# wifi_sensor.net
KiCad netlist of a schematic drawn in Altium Designer
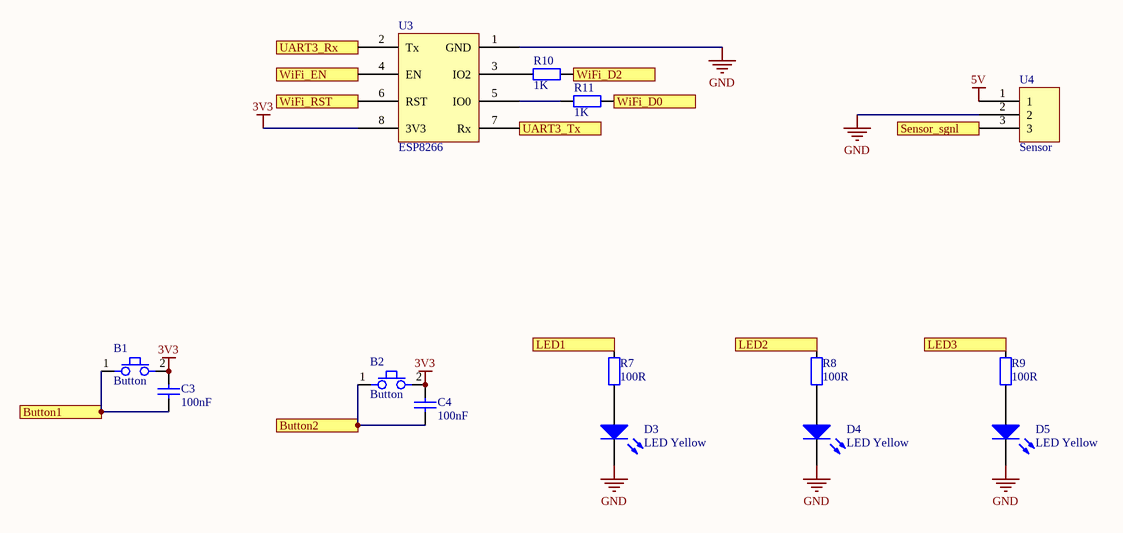
[diagram p0: wifi_sensor.SchDoc]

(export (version "E")
  (design (tool "Eeschema 10.0.6"))
  (components
    (comp (ref "B1") (value "Button") (footprint "Button") (libsource (lib "qlib") (part "Button")))
    (comp (ref "B2") (value "Button") (footprint "Button") (libsource (lib "qlib") (part "Button")))
    (comp (ref "C3")
      (value "100nF")
      (footprint "FP_0805_CAP_085")
      (description "Capacitor")
      (fields (field (name "TOLERANCE") "10%") (field (name "VOLTAGE") "50V"))
      (libsource (lib "hallglib") (part "CAP 100nF"))
    )
    (comp (ref "C4")
      (value "100nF")
      (footprint "FP_0805_CAP_085")
      (description "Capacitor")
      (fields (field (name "TOLERANCE") "10%") (field (name "VOLTAGE") "50V"))
      (libsource (lib "hallglib") (part "CAP 100nF"))
    )
    (comp (ref "D3")
      (value "LED Yellow")
      (footprint "FP_0805_LED_RED")
      (description "Yellow LED")
      (libsource (lib "hallglib") (part "LED Yellow"))
    )
    (comp (ref "D4")
      (value "LED Yellow")
      (footprint "FP_0805_LED_RED")
      (description "Yellow LED")
      (libsource (lib "hallglib") (part "LED Yellow"))
    )
    (comp (ref "D5")
      (value "LED Yellow")
      (footprint "FP_0805_LED_RED")
      (description "Yellow LED")
      (libsource (lib "hallglib") (part "LED Yellow"))
    )
    (comp (ref "R7")
      (value "100R")
      (footprint "FP_0805_RES")
      (description "Resistor")
      (fields (field (name "TOLERANCE") "5%") (field (name "POWER") "125mW"))
      (libsource (lib "hallglib") (part "RES 100R"))
    )
    (comp (ref "R8")
      (value "100R")
      (footprint "FP_0805_RES")
      (description "Resistor")
      (fields (field (name "TOLERANCE") "5%") (field (name "POWER") "125mW"))
      (libsource (lib "hallglib") (part "RES 100R"))
    )
    (comp (ref "R9")
      (value "100R")
      (footprint "FP_0805_RES")
      (description "Resistor")
      (fields (field (name "TOLERANCE") "5%") (field (name "POWER") "125mW"))
      (libsource (lib "hallglib") (part "RES 100R"))
    )
    (comp (ref "R10")
      (value "1K")
      (footprint "FP_0805_RES")
      (description "Resistor")
      (fields (field (name "TOLERANCE") "5%") (field (name "POWER") "125mW"))
      (libsource (lib "hallglib") (part "RES 1K"))
    )
    (comp (ref "R11")
      (value "1K")
      (footprint "FP_0805_RES")
      (description "Resistor")
      (fields (field (name "TOLERANCE") "5%") (field (name "POWER") "125mW"))
      (libsource (lib "hallglib") (part "RES 1K"))
    )
    (comp (ref "U3") (value "ESP8266") (footprint "HDR2X4") (libsource (lib "qlib") (part "ESP8266")))
    (comp (ref "U4") (value "Sensor") (footprint "3P_CONN_2mm") (libsource (lib "qlib") (part "Conn_3P")))
  )
  (nets
    (net (code "1") (name "/Button1") (class "Default")
      (node (ref "B1") (pin "1") (pinfunction "1_1") (pintype "passive"))
      (node (ref "C3") (pin "1") (pinfunction "1_1") (pintype "passive"))
    )
    (net (code "2") (name "/Button2") (class "Default")
      (node (ref "B2") (pin "1") (pinfunction "1_1") (pintype "passive"))
      (node (ref "C4") (pin "1") (pinfunction "1_1") (pintype "passive"))
    )
    (net (code "3") (name "/LED1") (class "Default")
      (node (ref "R7") (pin "2") (pinfunction "2_2") (pintype "passive"))
    )
    (net (code "4") (name "/LED2") (class "Default")
      (node (ref "R8") (pin "2") (pinfunction "2_2") (pintype "passive"))
    )
    (net (code "5") (name "/LED3") (class "Default")
      (node (ref "R9") (pin "2") (pinfunction "2_2") (pintype "passive"))
    )
    (net (code "6") (name "/Sensor_sgnl") (class "Default")
      (node (ref "U4") (pin "3") (pinfunction "3_3") (pintype "passive"))
    )
    (net (code "7") (name "/UART3_Rx") (class "Default")
      (node (ref "U3") (pin "2") (pinfunction "Tx_2") (pintype "passive"))
    )
    (net (code "8") (name "/UART3_Tx") (class "Default")
      (node (ref "U3") (pin "7") (pinfunction "Rx_7") (pintype "passive"))
    )
    (net (code "9") (name "/WiFi_D0") (class "Default")
      (node (ref "R11") (pin "2") (pinfunction "2_2") (pintype "passive"))
    )
    (net (code "10") (name "/WiFi_D2") (class "Default")
      (node (ref "R10") (pin "2") (pinfunction "2_2") (pintype "passive"))
    )
    (net (code "11") (name "/WiFi_EN") (class "Default")
      (node (ref "U3") (pin "4") (pinfunction "EN_4") (pintype "passive"))
    )
    (net (code "12") (name "/WiFi_RST") (class "Default")
      (node (ref "U3") (pin "6") (pinfunction "RST_6") (pintype "passive"))
    )
    (net (code "13") (name "3V3") (class "Default")
      (node (ref "B1") (pin "2") (pinfunction "2_2") (pintype "passive"))
      (node (ref "B2") (pin "2") (pinfunction "2_2") (pintype "passive"))
      (node (ref "C3") (pin "2") (pinfunction "2_2") (pintype "passive"))
      (node (ref "C4") (pin "2") (pinfunction "2_2") (pintype "passive"))
      (node (ref "U3") (pin "8") (pinfunction "3V3_8") (pintype "passive"))
    )
    (net (code "14") (name "5V") (class "Default")
      (node (ref "U4") (pin "1") (pinfunction "1_1") (pintype "passive"))
    )
    (net (code "15") (name "GND") (class "Default")
      (node (ref "D3") (pin "2") (pinfunction "K_2") (pintype "passive"))
      (node (ref "D4") (pin "2") (pinfunction "K_2") (pintype "passive"))
      (node (ref "D5") (pin "2") (pinfunction "K_2") (pintype "passive"))
      (node (ref "U3") (pin "1") (pinfunction "GND_1") (pintype "passive"))
      (node (ref "U4") (pin "2") (pinfunction "2_2") (pintype "passive"))
    )
    (net (code "16") (name "Net-(D3-A)") (class "Default")
      (node (ref "D3") (pin "1") (pinfunction "A_1") (pintype "passive"))
      (node (ref "R7") (pin "1") (pinfunction "1_1") (pintype "passive"))
    )
    (net (code "17") (name "Net-(D4-A)") (class "Default")
      (node (ref "D4") (pin "1") (pinfunction "A_1") (pintype "passive"))
      (node (ref "R8") (pin "1") (pinfunction "1_1") (pintype "passive"))
    )
    (net (code "18") (name "Net-(D5-A)") (class "Default")
      (node (ref "D5") (pin "1") (pinfunction "A_1") (pintype "passive"))
      (node (ref "R9") (pin "1") (pinfunction "1_1") (pintype "passive"))
    )
    (net (code "19") (name "Net-(U3-IO0)") (class "Default")
      (node (ref "R11") (pin "1") (pinfunction "1_1") (pintype "passive"))
      (node (ref "U3") (pin "5") (pinfunction "IO0_5") (pintype "passive"))
    )
    (net (code "20") (name "Net-(U3-IO2)") (class "Default")
      (node (ref "R10") (pin "1") (pinfunction "1_1") (pintype "passive"))
      (node (ref "U3") (pin "3") (pinfunction "IO2_3") (pintype "passive"))
    )
  )
)
